# ModuLoop_V1.net
KiCad netlist of a schematic drawn in Altium Designer
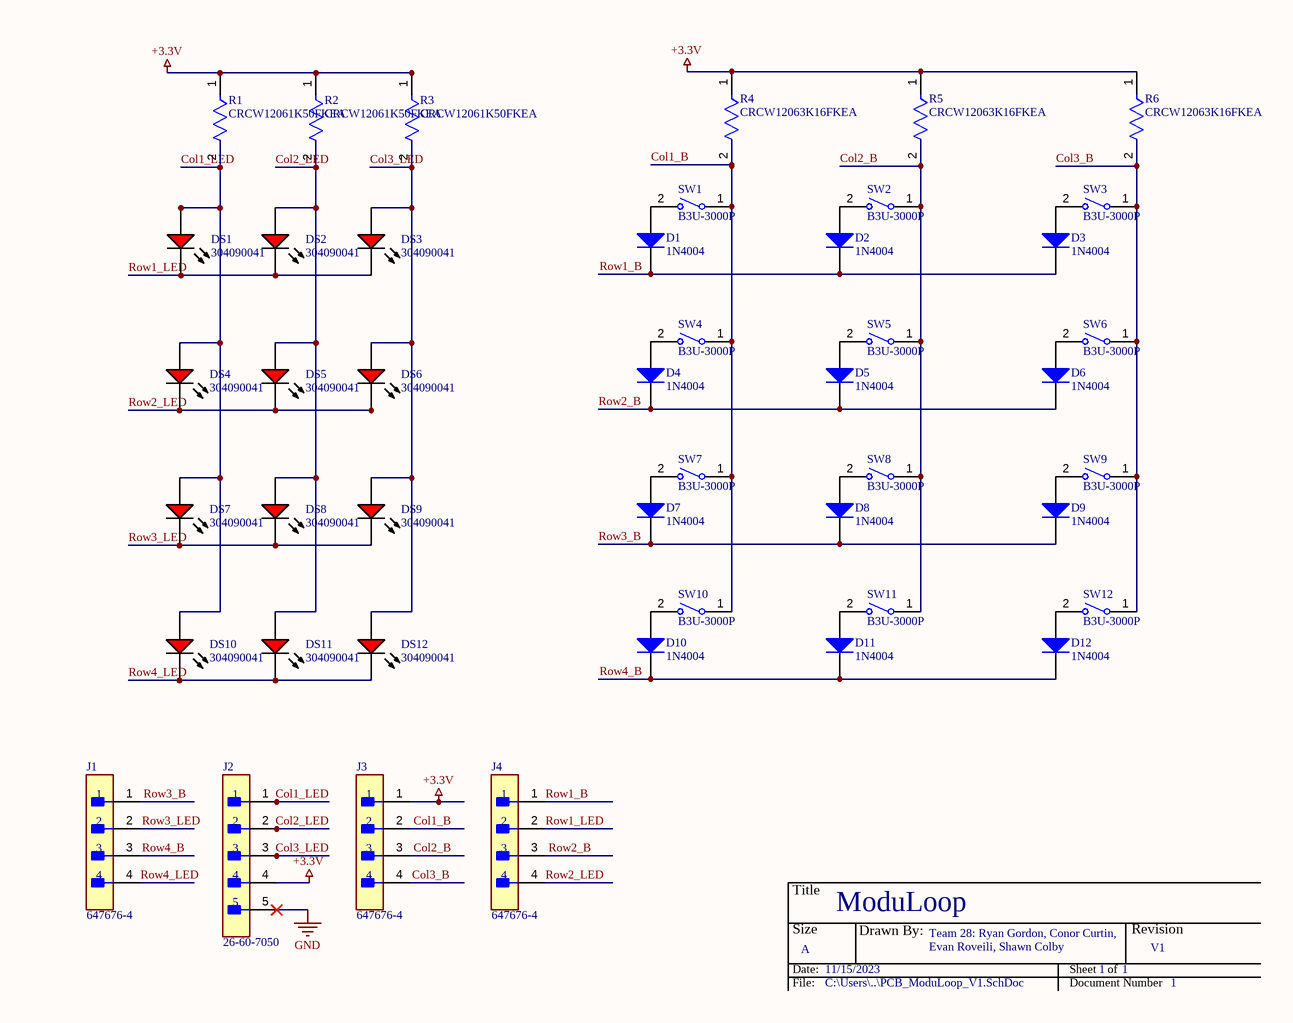
[diagram p0: ModuLoop_V1.SchDoc]

(export (version "E")
  (design (tool "Eeschema 10.0.6"))
  (components
    (comp (ref "D1")
      (value "1N4004")
      (footprint "FAIR-DO-41-2")
      (fields (field (name "MANUFACTURER") "Fairchild Semiconductor"))
      (libsource (lib "Ryamgordon") (part "D-AK-2"))
    )
    (comp (ref "D2")
      (value "1N4004")
      (footprint "FAIR-DO-41-2")
      (fields (field (name "MANUFACTURER") "Fairchild Semiconductor"))
      (libsource (lib "Ryamgordon") (part "D-AK-2"))
    )
    (comp (ref "D3")
      (value "1N4004")
      (footprint "FAIR-DO-41-2")
      (fields (field (name "MANUFACTURER") "Fairchild Semiconductor"))
      (libsource (lib "Ryamgordon") (part "D-AK-2"))
    )
    (comp (ref "D4")
      (value "1N4004")
      (footprint "FAIR-DO-41-2")
      (fields (field (name "MANUFACTURER") "Fairchild Semiconductor"))
      (libsource (lib "Ryamgordon") (part "D-AK-2"))
    )
    (comp (ref "D5")
      (value "1N4004")
      (footprint "FAIR-DO-41-2")
      (fields (field (name "MANUFACTURER") "Fairchild Semiconductor"))
      (libsource (lib "Ryamgordon") (part "D-AK-2"))
    )
    (comp (ref "D6")
      (value "1N4004")
      (footprint "FAIR-DO-41-2")
      (fields (field (name "MANUFACTURER") "Fairchild Semiconductor"))
      (libsource (lib "Ryamgordon") (part "D-AK-2"))
    )
    (comp (ref "D7")
      (value "1N4004")
      (footprint "FAIR-DO-41-2")
      (fields (field (name "MANUFACTURER") "Fairchild Semiconductor"))
      (libsource (lib "Ryamgordon") (part "D-AK-2"))
    )
    (comp (ref "D8")
      (value "1N4004")
      (footprint "FAIR-DO-41-2")
      (fields (field (name "MANUFACTURER") "Fairchild Semiconductor"))
      (libsource (lib "Ryamgordon") (part "D-AK-2"))
    )
    (comp (ref "D9")
      (value "1N4004")
      (footprint "FAIR-DO-41-2")
      (fields (field (name "MANUFACTURER") "Fairchild Semiconductor"))
      (libsource (lib "Ryamgordon") (part "D-AK-2"))
    )
    (comp (ref "D10")
      (value "1N4004")
      (footprint "FAIR-DO-41-2")
      (fields (field (name "MANUFACTURER") "Fairchild Semiconductor"))
      (libsource (lib "Ryamgordon") (part "D-AK-2"))
    )
    (comp (ref "D11")
      (value "1N4004")
      (footprint "FAIR-DO-41-2")
      (fields (field (name "MANUFACTURER") "Fairchild Semiconductor"))
      (libsource (lib "Ryamgordon") (part "D-AK-2"))
    )
    (comp (ref "D12")
      (value "1N4004")
      (footprint "FAIR-DO-41-2")
      (fields (field (name "MANUFACTURER") "Fairchild Semiconductor"))
      (libsource (lib "Ryamgordon") (part "D-AK-2"))
    )
    (comp (ref "DS1")
      (value "304090041")
      (footprint "LED-2P-2.28-3MM_A")
      (description "Red LED, 80 mW, 30 mA, -25 to 85 degC, 2-Pin THD")
      (fields (field (name "MANUFACTURER") "Shenzhen CGX"))
      (libsource (lib "Ryamgordon") (part "LED-RED-AK-2"))
    )
    (comp (ref "DS2")
      (value "304090041")
      (footprint "LED-2P-2.28-3MM_A")
      (description "Red LED, 80 mW, 30 mA, -25 to 85 degC, 2-Pin THD")
      (fields (field (name "MANUFACTURER") "Shenzhen CGX"))
      (libsource (lib "Ryamgordon") (part "LED-RED-AK-2"))
    )
    (comp (ref "DS3")
      (value "304090041")
      (footprint "LED-2P-2.28-3MM_A")
      (description "Red LED, 80 mW, 30 mA, -25 to 85 degC, 2-Pin THD")
      (fields (field (name "MANUFACTURER") "Shenzhen CGX"))
      (libsource (lib "Ryamgordon") (part "LED-RED-AK-2"))
    )
    (comp (ref "DS4")
      (value "304090041")
      (footprint "LED-2P-2.28-3MM_A")
      (description "Red LED, 80 mW, 30 mA, -25 to 85 degC, 2-Pin THD")
      (fields (field (name "MANUFACTURER") "Shenzhen CGX"))
      (libsource (lib "Ryamgordon") (part "LED-RED-AK-2"))
    )
    (comp (ref "DS5")
      (value "304090041")
      (footprint "LED-2P-2.28-3MM_A")
      (description "Red LED, 80 mW, 30 mA, -25 to 85 degC, 2-Pin THD")
      (fields (field (name "MANUFACTURER") "Shenzhen CGX"))
      (libsource (lib "Ryamgordon") (part "LED-RED-AK-2"))
    )
    (comp (ref "DS6")
      (value "304090041")
      (footprint "LED-2P-2.28-3MM_A")
      (description "Red LED, 80 mW, 30 mA, -25 to 85 degC, 2-Pin THD")
      (fields (field (name "MANUFACTURER") "Shenzhen CGX"))
      (libsource (lib "Ryamgordon") (part "LED-RED-AK-2"))
    )
    (comp (ref "DS7")
      (value "304090041")
      (footprint "LED-2P-2.28-3MM_A")
      (description "Red LED, 80 mW, 30 mA, -25 to 85 degC, 2-Pin THD")
      (fields (field (name "MANUFACTURER") "Shenzhen CGX"))
      (libsource (lib "Ryamgordon") (part "LED-RED-AK-2"))
    )
    (comp (ref "DS8")
      (value "304090041")
      (footprint "LED-2P-2.28-3MM_A")
      (description "Red LED, 80 mW, 30 mA, -25 to 85 degC, 2-Pin THD")
      (fields (field (name "MANUFACTURER") "Shenzhen CGX"))
      (libsource (lib "Ryamgordon") (part "LED-RED-AK-2"))
    )
    (comp (ref "DS9")
      (value "304090041")
      (footprint "LED-2P-2.28-3MM_A")
      (description "Red LED, 80 mW, 30 mA, -25 to 85 degC, 2-Pin THD")
      (fields (field (name "MANUFACTURER") "Shenzhen CGX"))
      (libsource (lib "Ryamgordon") (part "LED-RED-AK-2"))
    )
    (comp (ref "DS10")
      (value "304090041")
      (footprint "LED-2P-2.28-3MM_A")
      (description "Red LED, 80 mW, 30 mA, -25 to 85 degC, 2-Pin THD")
      (fields (field (name "MANUFACTURER") "Shenzhen CGX"))
      (libsource (lib "Ryamgordon") (part "LED-RED-AK-2"))
    )
    (comp (ref "DS11")
      (value "304090041")
      (footprint "LED-2P-2.28-3MM_A")
      (description "Red LED, 80 mW, 30 mA, -25 to 85 degC, 2-Pin THD")
      (fields (field (name "MANUFACTURER") "Shenzhen CGX"))
      (libsource (lib "Ryamgordon") (part "LED-RED-AK-2"))
    )
    (comp (ref "DS12")
      (value "304090041")
      (footprint "LED-2P-2.28-3MM_A")
      (description "Red LED, 80 mW, 30 mA, -25 to 85 degC, 2-Pin THD")
      (fields (field (name "MANUFACTURER") "Shenzhen CGX"))
      (libsource (lib "Ryamgordon") (part "LED-RED-AK-2"))
    )
    (comp (ref "J1")
      (value "647676-4")
      (footprint "FP-647676-4-MFG")
      (description "CONN HEADER R/A 4POS 3.96MM")
      (fields
        (field (name "OCTOPART") "https://octopart.com/647676-4-te+connectivity-41901901")
        (field (name "MANUFACTURER") "TE")
      )
      (libsource (lib "Altium Content Vault") (part "299a8cea1bdcbc3624fe62c390fa72c"))
    )
    (comp (ref "J2")
      (value "26-60-7050")
      (footprint "FP-26-60-7050-0")
      (description "CONN HEADER R/A 5POS 3.96MM")
      (libsource (lib "Altium Content Vault") (part "bf93c07fd2649a848d0ec8585582aab"))
    )
    (comp (ref "J3")
      (value "647676-4")
      (footprint "FP-647676-4-MFG")
      (description "CONN HEADER R/A 4POS 3.96MM")
      (fields
        (field (name "OCTOPART") "https://octopart.com/647676-4-te+connectivity-41901901")
        (field (name "MANUFACTURER") "TE")
      )
      (libsource (lib "Altium Content Vault") (part "299a8cea1bdcbc3624fe62c390fa72c"))
    )
    (comp (ref "J4")
      (value "647676-4")
      (footprint "FP-647676-4-MFG")
      (description "CONN HEADER R/A 4POS 3.96MM")
      (fields
        (field (name "OCTOPART") "https://octopart.com/647676-4-te+connectivity-41901901")
        (field (name "MANUFACTURER") "TE")
      )
      (libsource (lib "Altium Content Vault") (part "299a8cea1bdcbc3624fe62c390fa72c"))
    )
    (comp (ref "R1")
      (value "CRCW12061K50FKEA")
      (footprint "FP-CRCW1206-e3-IPC_C")
      (description "RES Thick Film, 1.5kΩ, 1%, 0.25W, 100ppm/°C, 1206")
      (fields (field (name "TOLERANCE") "1%"))
      (libsource (lib "Altium Content Vault") (part "1029c3af85768c4190bb7ad29bc67b5"))
    )
    (comp (ref "R2")
      (value "CRCW12061K50FKEA")
      (footprint "FP-CRCW1206-e3-IPC_C")
      (description "RES Thick Film, 1.5kΩ, 1%, 0.25W, 100ppm/°C, 1206")
      (fields (field (name "TOLERANCE") "1%"))
      (libsource (lib "Altium Content Vault") (part "1029c3af85768c4190bb7ad29bc67b5"))
    )
    (comp (ref "R3")
      (value "CRCW12061K50FKEA")
      (footprint "FP-CRCW1206-e3-IPC_C")
      (description "RES Thick Film, 1.5kΩ, 1%, 0.25W, 100ppm/°C, 1206")
      (fields (field (name "TOLERANCE") "1%"))
      (libsource (lib "Altium Content Vault") (part "1029c3af85768c4190bb7ad29bc67b5"))
    )
    (comp (ref "R4")
      (value "CRCW12063K16FKEA")
      (footprint "FP-CRCW1206-e3-MFG")
      (description "RES Thick Film, 3.16kΩ, 1%, 0.25W, 100ppm/°C, 1206")
      (fields (field (name "TOLERANCE") "1%"))
      (libsource (lib "Altium Content Vault") (part "1029c3af85768c4190bb7ad29bc67b5"))
    )
    (comp (ref "R5")
      (value "CRCW12063K16FKEA")
      (footprint "FP-CRCW1206-e3-MFG")
      (description "RES Thick Film, 3.16kΩ, 1%, 0.25W, 100ppm/°C, 1206")
      (fields (field (name "TOLERANCE") "1%"))
      (libsource (lib "Altium Content Vault") (part "1029c3af85768c4190bb7ad29bc67b5"))
    )
    (comp (ref "R6")
      (value "CRCW12063K16FKEA")
      (footprint "FP-CRCW1206-e3-MFG")
      (description "RES Thick Film, 3.16kΩ, 1%, 0.25W, 100ppm/°C, 1206")
      (fields (field (name "TOLERANCE") "1%"))
      (libsource (lib "Altium Content Vault") (part "1029c3af85768c4190bb7ad29bc67b5"))
    )
    (comp (ref "SW1")
      (value "B3U-3000P")
      (footprint "OMRON-B3U-3000P_V")
      (description "Tactile Switch, SPST-NO, 0.05 A, 12 V, -25 to 70 degC, 2-Pin SMD, RoHS, Tape and Reel")
      (fields (field (name "MANUFACTURER") "Omron Electronic Components"))
      (libsource (lib "Ryamgordon") (part "SW-SPST-2_C"))
    )
    (comp (ref "SW2")
      (value "B3U-3000P")
      (footprint "OMRON-B3U-3000P_V")
      (description "Tactile Switch, SPST-NO, 0.05 A, 12 V, -25 to 70 degC, 2-Pin SMD, RoHS, Tape and Reel")
      (fields (field (name "MANUFACTURER") "Omron Electronic Components"))
      (libsource (lib "Ryamgordon") (part "SW-SPST-2_C"))
    )
    (comp (ref "SW3")
      (value "B3U-3000P")
      (footprint "OMRON-B3U-3000P_V")
      (description "Tactile Switch, SPST-NO, 0.05 A, 12 V, -25 to 70 degC, 2-Pin SMD, RoHS, Tape and Reel")
      (fields (field (name "MANUFACTURER") "Omron Electronic Components"))
      (libsource (lib "Ryamgordon") (part "SW-SPST-2_C"))
    )
    (comp (ref "SW4")
      (value "B3U-3000P")
      (footprint "OMRON-B3U-3000P_V")
      (description "Tactile Switch, SPST-NO, 0.05 A, 12 V, -25 to 70 degC, 2-Pin SMD, RoHS, Tape and Reel")
      (fields (field (name "MANUFACTURER") "Omron Electronic Components"))
      (libsource (lib "Ryamgordon") (part "SW-SPST-2_C"))
    )
    (comp (ref "SW5")
      (value "B3U-3000P")
      (footprint "OMRON-B3U-3000P_V")
      (description "Tactile Switch, SPST-NO, 0.05 A, 12 V, -25 to 70 degC, 2-Pin SMD, RoHS, Tape and Reel")
      (fields (field (name "MANUFACTURER") "Omron Electronic Components"))
      (libsource (lib "Ryamgordon") (part "SW-SPST-2_C"))
    )
    (comp (ref "SW6")
      (value "B3U-3000P")
      (footprint "OMRON-B3U-3000P_V")
      (description "Tactile Switch, SPST-NO, 0.05 A, 12 V, -25 to 70 degC, 2-Pin SMD, RoHS, Tape and Reel")
      (fields (field (name "MANUFACTURER") "Omron Electronic Components"))
      (libsource (lib "Ryamgordon") (part "SW-SPST-2_C"))
    )
    (comp (ref "SW7")
      (value "B3U-3000P")
      (footprint "OMRON-B3U-3000P_V")
      (description "Tactile Switch, SPST-NO, 0.05 A, 12 V, -25 to 70 degC, 2-Pin SMD, RoHS, Tape and Reel")
      (fields (field (name "MANUFACTURER") "Omron Electronic Components"))
      (libsource (lib "Ryamgordon") (part "SW-SPST-2_C"))
    )
    (comp (ref "SW8")
      (value "B3U-3000P")
      (footprint "OMRON-B3U-3000P_V")
      (description "Tactile Switch, SPST-NO, 0.05 A, 12 V, -25 to 70 degC, 2-Pin SMD, RoHS, Tape and Reel")
      (fields (field (name "MANUFACTURER") "Omron Electronic Components"))
      (libsource (lib "Ryamgordon") (part "SW-SPST-2_C"))
    )
    (comp (ref "SW9")
      (value "B3U-3000P")
      (footprint "OMRON-B3U-3000P_V")
      (description "Tactile Switch, SPST-NO, 0.05 A, 12 V, -25 to 70 degC, 2-Pin SMD, RoHS, Tape and Reel")
      (fields (field (name "MANUFACTURER") "Omron Electronic Components"))
      (libsource (lib "Ryamgordon") (part "SW-SPST-2_C"))
    )
    (comp (ref "SW10")
      (value "B3U-3000P")
      (footprint "OMRON-B3U-3000P_V")
      (description "Tactile Switch, SPST-NO, 0.05 A, 12 V, -25 to 70 degC, 2-Pin SMD, RoHS, Tape and Reel")
      (fields (field (name "MANUFACTURER") "Omron Electronic Components"))
      (libsource (lib "Ryamgordon") (part "SW-SPST-2_C"))
    )
    (comp (ref "SW11")
      (value "B3U-3000P")
      (footprint "OMRON-B3U-3000P_V")
      (description "Tactile Switch, SPST-NO, 0.05 A, 12 V, -25 to 70 degC, 2-Pin SMD, RoHS, Tape and Reel")
      (fields (field (name "MANUFACTURER") "Omron Electronic Components"))
      (libsource (lib "Ryamgordon") (part "SW-SPST-2_C"))
    )
    (comp (ref "SW12")
      (value "B3U-3000P")
      (footprint "OMRON-B3U-3000P_V")
      (description "Tactile Switch, SPST-NO, 0.05 A, 12 V, -25 to 70 degC, 2-Pin SMD, RoHS, Tape and Reel")
      (fields (field (name "MANUFACTURER") "Omron Electronic Components"))
      (libsource (lib "Ryamgordon") (part "SW-SPST-2_C"))
    )
  )
  (nets
    (net (code "1") (name "+3.3V") (class "Default")
      (node (ref "J2") (pin "4") (pinfunction "4_4") (pintype "passive"))
      (node (ref "J3") (pin "1") (pinfunction "1_1") (pintype "passive"))
      (node (ref "R1") (pin "1") (pinfunction "1_1") (pintype "passive"))
      (node (ref "R2") (pin "1") (pinfunction "1_1") (pintype "passive"))
      (node (ref "R3") (pin "1") (pinfunction "1_1") (pintype "passive"))
      (node (ref "R4") (pin "1") (pinfunction "1_1") (pintype "passive"))
      (node (ref "R5") (pin "1") (pinfunction "1_1") (pintype "passive"))
      (node (ref "R6") (pin "1") (pinfunction "1_1") (pintype "passive"))
    )
    (net (code "3") (name "/Col1_B") (class "Default")
      (node (ref "J3") (pin "2") (pinfunction "2_2") (pintype "passive"))
      (node (ref "R4") (pin "2") (pinfunction "2_2") (pintype "passive"))
      (node (ref "SW1") (pin "1") (pinfunction "1_1") (pintype "passive"))
      (node (ref "SW10") (pin "1") (pinfunction "1_1") (pintype "passive"))
      (node (ref "SW4") (pin "1") (pinfunction "1_1") (pintype "passive"))
      (node (ref "SW7") (pin "1") (pinfunction "1_1") (pintype "passive"))
    )
    (net (code "4") (name "/Col1_LED") (class "Default")
      (node (ref "DS1") (pin "1") (pinfunction "A_1") (pintype "passive"))
      (node (ref "DS10") (pin "1") (pinfunction "A_1") (pintype "passive"))
      (node (ref "DS4") (pin "1") (pinfunction "A_1") (pintype "passive"))
      (node (ref "DS7") (pin "1") (pinfunction "A_1") (pintype "passive"))
      (node (ref "J2") (pin "1") (pinfunction "1_1") (pintype "passive"))
      (node (ref "R1") (pin "2") (pinfunction "2_2") (pintype "passive"))
    )
    (net (code "5") (name "/Col2_B") (class "Default")
      (node (ref "J3") (pin "3") (pinfunction "3_3") (pintype "passive"))
      (node (ref "R5") (pin "2") (pinfunction "2_2") (pintype "passive"))
      (node (ref "SW11") (pin "1") (pinfunction "1_1") (pintype "passive"))
      (node (ref "SW2") (pin "1") (pinfunction "1_1") (pintype "passive"))
      (node (ref "SW5") (pin "1") (pinfunction "1_1") (pintype "passive"))
      (node (ref "SW8") (pin "1") (pinfunction "1_1") (pintype "passive"))
    )
    (net (code "6") (name "/Col2_LED") (class "Default")
      (node (ref "DS11") (pin "1") (pinfunction "A_1") (pintype "passive"))
      (node (ref "DS2") (pin "1") (pinfunction "A_1") (pintype "passive"))
      (node (ref "DS5") (pin "1") (pinfunction "A_1") (pintype "passive"))
      (node (ref "DS8") (pin "1") (pinfunction "A_1") (pintype "passive"))
      (node (ref "J2") (pin "2") (pinfunction "2_2") (pintype "passive"))
      (node (ref "R2") (pin "2") (pinfunction "2_2") (pintype "passive"))
    )
    (net (code "7") (name "/Col3_B") (class "Default")
      (node (ref "J3") (pin "4") (pinfunction "4_4") (pintype "passive"))
      (node (ref "R6") (pin "2") (pinfunction "2_2") (pintype "passive"))
      (node (ref "SW12") (pin "1") (pinfunction "1_1") (pintype "passive"))
      (node (ref "SW3") (pin "1") (pinfunction "1_1") (pintype "passive"))
      (node (ref "SW6") (pin "1") (pinfunction "1_1") (pintype "passive"))
      (node (ref "SW9") (pin "1") (pinfunction "1_1") (pintype "passive"))
    )
    (net (code "8") (name "/Col3_LED") (class "Default")
      (node (ref "DS12") (pin "1") (pinfunction "A_1") (pintype "passive"))
      (node (ref "DS3") (pin "1") (pinfunction "A_1") (pintype "passive"))
      (node (ref "DS6") (pin "1") (pinfunction "A_1") (pintype "passive"))
      (node (ref "DS9") (pin "1") (pinfunction "A_1") (pintype "passive"))
      (node (ref "J2") (pin "3") (pinfunction "3_3") (pintype "passive"))
      (node (ref "R3") (pin "2") (pinfunction "2_2") (pintype "passive"))
    )
    (net (code "9") (name "/Row1_B") (class "Default")
      (node (ref "D1") (pin "2") (pinfunction "K_2") (pintype "passive"))
      (node (ref "D2") (pin "2") (pinfunction "K_2") (pintype "passive"))
      (node (ref "D3") (pin "2") (pinfunction "K_2") (pintype "passive"))
      (node (ref "J4") (pin "1") (pinfunction "1_1") (pintype "passive"))
    )
    (net (code "10") (name "/Row1_LED") (class "Default")
      (node (ref "DS1") (pin "2") (pinfunction "K_2") (pintype "passive"))
      (node (ref "DS2") (pin "2") (pinfunction "K_2") (pintype "passive"))
      (node (ref "DS3") (pin "2") (pinfunction "K_2") (pintype "passive"))
      (node (ref "J4") (pin "2") (pinfunction "2_2") (pintype "passive"))
    )
    (net (code "11") (name "/Row2_B") (class "Default")
      (node (ref "D4") (pin "2") (pinfunction "K_2") (pintype "passive"))
      (node (ref "D5") (pin "2") (pinfunction "K_2") (pintype "passive"))
      (node (ref "D6") (pin "2") (pinfunction "K_2") (pintype "passive"))
      (node (ref "J4") (pin "3") (pinfunction "3_3") (pintype "passive"))
    )
    (net (code "12") (name "/Row2_LED") (class "Default")
      (node (ref "DS4") (pin "2") (pinfunction "K_2") (pintype "passive"))
      (node (ref "DS5") (pin "2") (pinfunction "K_2") (pintype "passive"))
      (node (ref "DS6") (pin "2") (pinfunction "K_2") (pintype "passive"))
      (node (ref "J4") (pin "4") (pinfunction "4_4") (pintype "passive"))
    )
    (net (code "13") (name "/Row3_B") (class "Default")
      (node (ref "D7") (pin "2") (pinfunction "K_2") (pintype "passive"))
      (node (ref "D8") (pin "2") (pinfunction "K_2") (pintype "passive"))
      (node (ref "D9") (pin "2") (pinfunction "K_2") (pintype "passive"))
      (node (ref "J1") (pin "1") (pinfunction "1_1") (pintype "passive"))
    )
    (net (code "14") (name "/Row3_LED") (class "Default")
      (node (ref "DS7") (pin "2") (pinfunction "K_2") (pintype "passive"))
      (node (ref "DS8") (pin "2") (pinfunction "K_2") (pintype "passive"))
      (node (ref "DS9") (pin "2") (pinfunction "K_2") (pintype "passive"))
      (node (ref "J1") (pin "2") (pinfunction "2_2") (pintype "passive"))
    )
    (net (code "15") (name "/Row4_B") (class "Default")
      (node (ref "D10") (pin "2") (pinfunction "K_2") (pintype "passive"))
      (node (ref "D11") (pin "2") (pinfunction "K_2") (pintype "passive"))
      (node (ref "D12") (pin "2") (pinfunction "K_2") (pintype "passive"))
      (node (ref "J1") (pin "3") (pinfunction "3_3") (pintype "passive"))
    )
    (net (code "16") (name "/Row4_LED") (class "Default")
      (node (ref "DS10") (pin "2") (pinfunction "K_2") (pintype "passive"))
      (node (ref "DS11") (pin "2") (pinfunction "K_2") (pintype "passive"))
      (node (ref "DS12") (pin "2") (pinfunction "K_2") (pintype "passive"))
      (node (ref "J1") (pin "4") (pinfunction "4_4") (pintype "passive"))
    )
    (net (code "17") (name "GND") (class "Default")
      (node (ref "J2") (pin "5") (pinfunction "5_5") (pintype "passive"))
    )
    (net (code "18") (name "Net-(D1-A)") (class "Default")
      (node (ref "D1") (pin "1") (pinfunction "A_1") (pintype "passive"))
      (node (ref "SW1") (pin "2") (pinfunction "2_2") (pintype "passive"))
    )
    (net (code "19") (name "Net-(D2-A)") (class "Default")
      (node (ref "D2") (pin "1") (pinfunction "A_1") (pintype "passive"))
      (node (ref "SW2") (pin "2") (pinfunction "2_2") (pintype "passive"))
    )
    (net (code "20") (name "Net-(D3-A)") (class "Default")
      (node (ref "D3") (pin "1") (pinfunction "A_1") (pintype "passive"))
      (node (ref "SW3") (pin "2") (pinfunction "2_2") (pintype "passive"))
    )
    (net (code "21") (name "Net-(D4-A)") (class "Default")
      (node (ref "D4") (pin "1") (pinfunction "A_1") (pintype "passive"))
      (node (ref "SW4") (pin "2") (pinfunction "2_2") (pintype "passive"))
    )
    (net (code "22") (name "Net-(D5-A)") (class "Default")
      (node (ref "D5") (pin "1") (pinfunction "A_1") (pintype "passive"))
      (node (ref "SW5") (pin "2") (pinfunction "2_2") (pintype "passive"))
    )
    (net (code "23") (name "Net-(D6-A)") (class "Default")
      (node (ref "D6") (pin "1") (pinfunction "A_1") (pintype "passive"))
      (node (ref "SW6") (pin "2") (pinfunction "2_2") (pintype "passive"))
    )
    (net (code "24") (name "Net-(D7-A)") (class "Default")
      (node (ref "D7") (pin "1") (pinfunction "A_1") (pintype "passive"))
      (node (ref "SW7") (pin "2") (pinfunction "2_2") (pintype "passive"))
    )
    (net (code "25") (name "Net-(D8-A)") (class "Default")
      (node (ref "D8") (pin "1") (pinfunction "A_1") (pintype "passive"))
      (node (ref "SW8") (pin "2") (pinfunction "2_2") (pintype "passive"))
    )
    (net (code "26") (name "Net-(D9-A)") (class "Default")
      (node (ref "D9") (pin "1") (pinfunction "A_1") (pintype "passive"))
      (node (ref "SW9") (pin "2") (pinfunction "2_2") (pintype "passive"))
    )
    (net (code "27") (name "Net-(D10-A)") (class "Default")
      (node (ref "D10") (pin "1") (pinfunction "A_1") (pintype "passive"))
      (node (ref "SW10") (pin "2") (pinfunction "2_2") (pintype "passive"))
    )
    (net (code "28") (name "Net-(D11-A)") (class "Default")
      (node (ref "D11") (pin "1") (pinfunction "A_1") (pintype "passive"))
      (node (ref "SW11") (pin "2") (pinfunction "2_2") (pintype "passive"))
    )
    (net (code "29") (name "Net-(D12-A)") (class "Default")
      (node (ref "D12") (pin "1") (pinfunction "A_1") (pintype "passive"))
      (node (ref "SW12") (pin "2") (pinfunction "2_2") (pintype "passive"))
    )
  )
)
